# 00A-024_FRDM_Protoboard.net
KiCad netlist of a schematic drawn in EAGLE
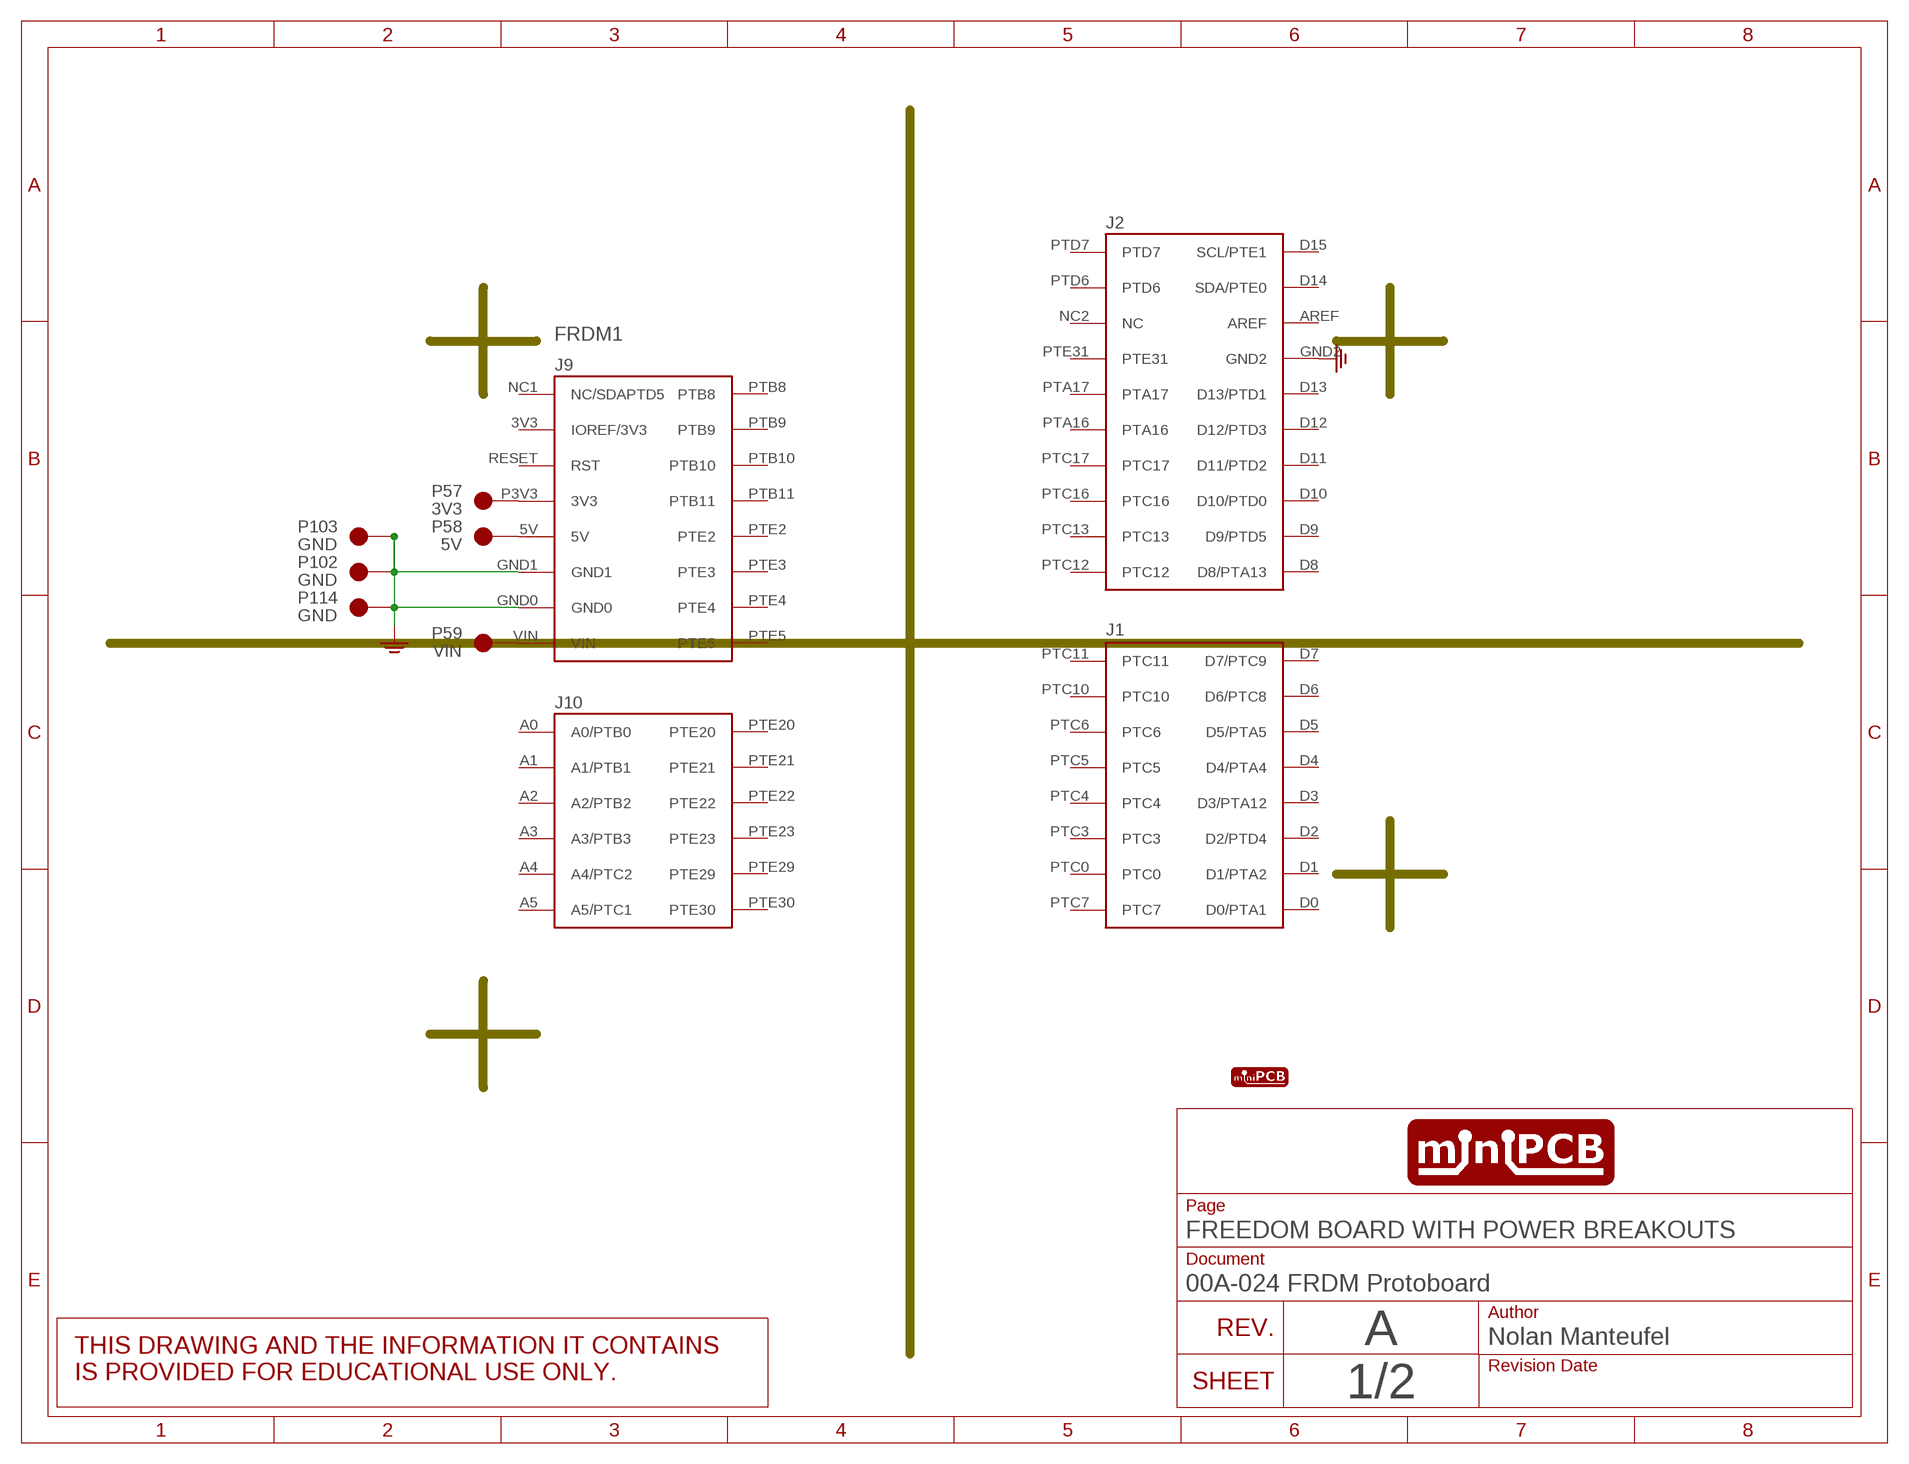
[diagram p0: schematic, sheet 1]
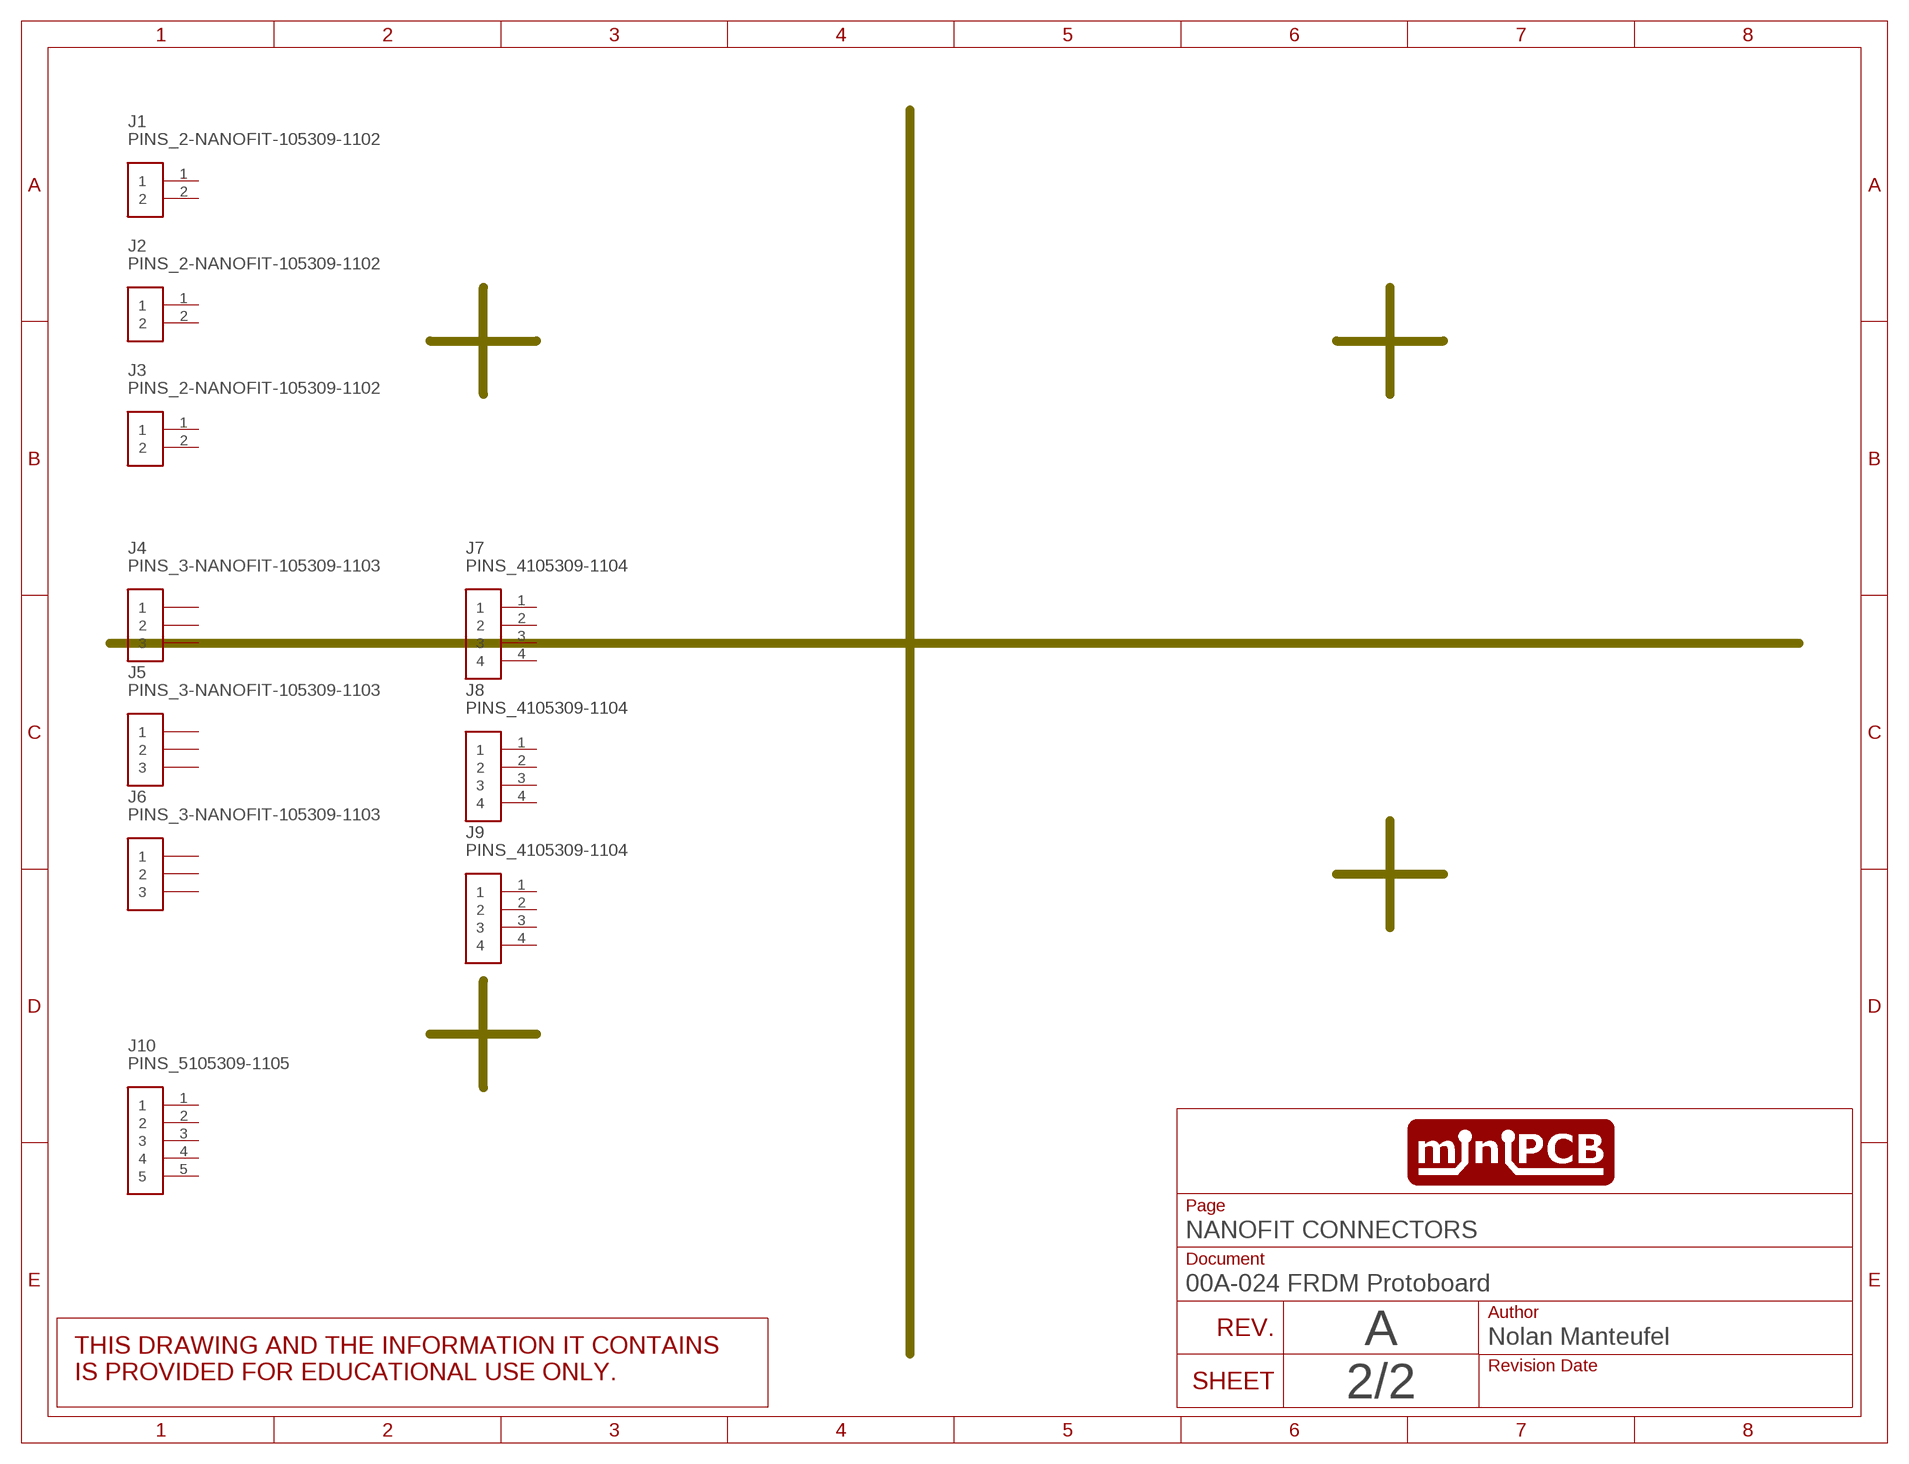
[diagram p1: schematic, sheet 2]

(export (version "E")
  (design (tool "Eeschema 10.0.6"))
  (components
    (comp (ref "FRDM1")
      (value "FRDM-KL25ZNORMAL")
      (footprint "eagle-import:FRDM_KL25Z_NORMAL")
      (fields (field (name "MF") "NXP USA") (field (name "MP") "FRDM-KL25Z"))
      (libsource (lib "eagle-import") (part "FRDM-KL25ZNORMAL"))
    )
    (comp (ref "P57")
      (value "3V3")
      (footprint "eagle-import:PINS_1-3P_VALUE")
      (libsource (lib "eagle-import") (part "PINS_13P_VALUE"))
    )
    (comp (ref "P58")
      (value "5V")
      (footprint "eagle-import:PINS_1-3P_VALUE")
      (libsource (lib "eagle-import") (part "PINS_13P_VALUE"))
    )
    (comp (ref "P59")
      (value "VIN")
      (footprint "eagle-import:PINS_1-3P_VALUE")
      (libsource (lib "eagle-import") (part "PINS_13P_VALUE"))
    )
    (comp (ref "P102")
      (value "GND")
      (footprint "eagle-import:PINS_1-3P_VALUE")
      (libsource (lib "eagle-import") (part "PINS_13P_VALUE"))
    )
    (comp (ref "P103")
      (value "GND")
      (footprint "eagle-import:PINS_1-3P_VALUE")
      (libsource (lib "eagle-import") (part "PINS_13P_VALUE"))
    )
    (comp (ref "P114")
      (value "GND")
      (footprint "eagle-import:PINS_1-3P_VALUE")
      (libsource (lib "eagle-import") (part "PINS_13P_VALUE"))
    )
    (comp (ref "U$1")
      (value "MINIPCB_LOGO")
      (footprint "eagle-import:MINIPCB-LOGO")
      (libsource (lib "eagle-import") (part "MINIPCB_LOGO"))
    )
    (comp (ref "J1")
      (value "PINS_2-NANOFIT-105309-1102")
      (footprint "eagle-import:PINS_2-NANOFIT")
      (libsource (lib "eagle-import") (part "PINS_2-NANOFIT-105309-1102"))
    )
    (comp (ref "J2")
      (value "PINS_2-NANOFIT-105309-1102")
      (footprint "eagle-import:PINS_2-NANOFIT")
      (libsource (lib "eagle-import") (part "PINS_2-NANOFIT-105309-1102"))
    )
    (comp (ref "J3")
      (value "PINS_2-NANOFIT-105309-1102")
      (footprint "eagle-import:PINS_2-NANOFIT")
      (libsource (lib "eagle-import") (part "PINS_2-NANOFIT-105309-1102"))
    )
    (comp (ref "J4")
      (value "PINS_3-NANOFIT-105309-1103")
      (footprint "eagle-import:PINS_3-NANOFIT")
      (libsource (lib "eagle-import") (part "PINS_3-NANOFIT-105309-1103"))
    )
    (comp (ref "J5")
      (value "PINS_3-NANOFIT-105309-1103")
      (footprint "eagle-import:PINS_3-NANOFIT")
      (libsource (lib "eagle-import") (part "PINS_3-NANOFIT-105309-1103"))
    )
    (comp (ref "J6")
      (value "PINS_3-NANOFIT-105309-1103")
      (footprint "eagle-import:PINS_3-NANOFIT")
      (libsource (lib "eagle-import") (part "PINS_3-NANOFIT-105309-1103"))
    )
    (comp (ref "J7")
      (value "PINS_4105309-1104")
      (footprint "eagle-import:PINS_4-NANOFIT")
      (libsource (lib "eagle-import") (part "PINS_4105309-1104"))
    )
    (comp (ref "J8")
      (value "PINS_4105309-1104")
      (footprint "eagle-import:PINS_4-NANOFIT")
      (libsource (lib "eagle-import") (part "PINS_4105309-1104"))
    )
    (comp (ref "J9")
      (value "PINS_4105309-1104")
      (footprint "eagle-import:PINS_4-NANOFIT")
      (libsource (lib "eagle-import") (part "PINS_4105309-1104"))
    )
    (comp (ref "J10")
      (value "PINS_5105309-1105")
      (footprint "eagle-import:PINS_5-NANOFIT")
      (libsource (lib "eagle-import") (part "PINS_5105309-1105"))
    )
  )
  (nets
    (net (code "1") (name "GND") (class "Default")
      (node (ref "FRDM1") (pin "GND0") (pinfunction "GND0_GND0") (pintype "bidirectional"))
      (node (ref "FRDM1") (pin "GND1") (pinfunction "GND1_GND1") (pintype "bidirectional"))
      (node (ref "FRDM1") (pin "GND2") (pinfunction "GND2_GND2") (pintype "bidirectional"))
      (node (ref "P102") (pin "1") (pinfunction "1_1") (pintype "bidirectional"))
      (node (ref "P102") (pin "2") (pinfunction "1_2") (pintype "bidirectional"))
      (node (ref "P102") (pin "3") (pinfunction "1_3") (pintype "bidirectional"))
      (node (ref "P103") (pin "1") (pinfunction "1_1") (pintype "bidirectional"))
      (node (ref "P103") (pin "2") (pinfunction "1_2") (pintype "bidirectional"))
      (node (ref "P103") (pin "3") (pinfunction "1_3") (pintype "bidirectional"))
      (node (ref "P114") (pin "1") (pinfunction "1_1") (pintype "bidirectional"))
      (node (ref "P114") (pin "2") (pinfunction "1_2") (pintype "bidirectional"))
      (node (ref "P114") (pin "3") (pinfunction "1_3") (pintype "bidirectional"))
    )
    (net (code "2") (name "Net-(FRDM1-3V3)") (class "Default")
      (node (ref "FRDM1") (pin "P3V3") (pinfunction "3V3_P3V3") (pintype "bidirectional"))
      (node (ref "P57") (pin "1") (pinfunction "1_1") (pintype "bidirectional"))
      (node (ref "P57") (pin "2") (pinfunction "1_2") (pintype "bidirectional"))
      (node (ref "P57") (pin "3") (pinfunction "1_3") (pintype "bidirectional"))
    )
    (net (code "3") (name "Net-(FRDM1-Pad5V)") (class "Default")
      (node (ref "FRDM1") (pin "5V") (pinfunction "5V_5V") (pintype "bidirectional"))
      (node (ref "P58") (pin "1") (pinfunction "1_1") (pintype "bidirectional"))
      (node (ref "P58") (pin "2") (pinfunction "1_2") (pintype "bidirectional"))
      (node (ref "P58") (pin "3") (pinfunction "1_3") (pintype "bidirectional"))
    )
    (net (code "4") (name "Net-(FRDM1-PadVIN)") (class "Default")
      (node (ref "FRDM1") (pin "VIN") (pinfunction "VIN_VIN") (pintype "bidirectional"))
      (node (ref "P59") (pin "1") (pinfunction "1_1") (pintype "bidirectional"))
      (node (ref "P59") (pin "2") (pinfunction "1_2") (pintype "bidirectional"))
      (node (ref "P59") (pin "3") (pinfunction "1_3") (pintype "bidirectional"))
    )
    (net (code "5") (name "unconnected-(FRDM1-A0{slash}PTB0-PadA0)") (class "Default")
      (node (ref "FRDM1") (pin "A0") (pinfunction "A0/PTB0_A0") (pintype "bidirectional"))
    )
    (net (code "6") (name "unconnected-(FRDM1-A1{slash}PTB1-PadA1)") (class "Default")
      (node (ref "FRDM1") (pin "A1") (pinfunction "A1/PTB1_A1") (pintype "bidirectional"))
    )
    (net (code "7") (name "unconnected-(FRDM1-A2{slash}PTB2-PadA2)") (class "Default")
      (node (ref "FRDM1") (pin "A2") (pinfunction "A2/PTB2_A2") (pintype "bidirectional"))
    )
    (net (code "8") (name "unconnected-(FRDM1-A3{slash}PTB3-PadA3)") (class "Default")
      (node (ref "FRDM1") (pin "A3") (pinfunction "A3/PTB3_A3") (pintype "bidirectional"))
    )
    (net (code "9") (name "unconnected-(FRDM1-A4{slash}PTC2-PadA4)") (class "Default")
      (node (ref "FRDM1") (pin "A4") (pinfunction "A4/PTC2_A4") (pintype "bidirectional"))
    )
    (net (code "10") (name "unconnected-(FRDM1-A5{slash}PTC1-PadA5)") (class "Default")
      (node (ref "FRDM1") (pin "A5") (pinfunction "A5/PTC1_A5") (pintype "bidirectional"))
    )
    (net (code "11") (name "unconnected-(FRDM1-D0{slash}PTA1-PadD0)") (class "Default")
      (node (ref "FRDM1") (pin "D0") (pinfunction "D0/PTA1_D0") (pintype "bidirectional"))
    )
    (net (code "12") (name "unconnected-(FRDM1-D1{slash}PTA2-PadD1)") (class "Default")
      (node (ref "FRDM1") (pin "D1") (pinfunction "D1/PTA2_D1") (pintype "bidirectional"))
    )
    (net (code "13") (name "unconnected-(FRDM1-D2{slash}PTD4-PadD2)") (class "Default")
      (node (ref "FRDM1") (pin "D2") (pinfunction "D2/PTD4_D2") (pintype "bidirectional"))
    )
    (net (code "14") (name "unconnected-(FRDM1-D3{slash}PTA12-PadD3)") (class "Default")
      (node (ref "FRDM1") (pin "D3") (pinfunction "D3/PTA12_D3") (pintype "bidirectional"))
    )
    (net (code "15") (name "unconnected-(FRDM1-D4{slash}PTA4-PadD4)") (class "Default")
      (node (ref "FRDM1") (pin "D4") (pinfunction "D4/PTA4_D4") (pintype "bidirectional"))
    )
    (net (code "16") (name "unconnected-(FRDM1-D5{slash}PTA5-PadD5)") (class "Default")
      (node (ref "FRDM1") (pin "D5") (pinfunction "D5/PTA5_D5") (pintype "bidirectional"))
    )
    (net (code "17") (name "unconnected-(FRDM1-D6{slash}PTC8-PadD6)") (class "Default")
      (node (ref "FRDM1") (pin "D6") (pinfunction "D6/PTC8_D6") (pintype "bidirectional"))
    )
    (net (code "18") (name "unconnected-(FRDM1-D7{slash}PTC9-PadD7)") (class "Default")
      (node (ref "FRDM1") (pin "D7") (pinfunction "D7/PTC9_D7") (pintype "bidirectional"))
    )
    (net (code "19") (name "unconnected-(FRDM1-D8{slash}PTA13-PadD8)") (class "Default")
      (node (ref "FRDM1") (pin "D8") (pinfunction "D8/PTA13_D8") (pintype "bidirectional"))
    )
    (net (code "20") (name "unconnected-(FRDM1-D9{slash}PTD5-PadD9)") (class "Default")
      (node (ref "FRDM1") (pin "D9") (pinfunction "D9/PTD5_D9") (pintype "bidirectional"))
    )
    (net (code "21") (name "unconnected-(FRDM1-D10{slash}PTD0-PadD10)") (class "Default")
      (node (ref "FRDM1") (pin "D10") (pinfunction "D10/PTD0_D10") (pintype "bidirectional"))
    )
    (net (code "22") (name "unconnected-(FRDM1-D11{slash}PTD2-PadD11)") (class "Default")
      (node (ref "FRDM1") (pin "D11") (pinfunction "D11/PTD2_D11") (pintype "bidirectional"))
    )
    (net (code "23") (name "unconnected-(FRDM1-D12{slash}PTD3-PadD12)") (class "Default")
      (node (ref "FRDM1") (pin "D12") (pinfunction "D12/PTD3_D12") (pintype "bidirectional"))
    )
    (net (code "24") (name "unconnected-(FRDM1-D13{slash}PTD1-PadD13)") (class "Default")
      (node (ref "FRDM1") (pin "D13") (pinfunction "D13/PTD1_D13") (pintype "bidirectional"))
    )
    (net (code "25") (name "unconnected-(FRDM1-IOREF{slash}3V3-Pad3V3)") (class "Default")
      (node (ref "FRDM1") (pin "3V3") (pinfunction "IOREF/3V3_3V3") (pintype "bidirectional"))
    )
    (net (code "26") (name "unconnected-(FRDM1-NC-PadNC2)") (class "Default")
      (node (ref "FRDM1") (pin "NC2") (pinfunction "NC_NC2") (pintype "bidirectional"))
    )
    (net (code "27") (name "unconnected-(FRDM1-NC{slash}SDAPTD5-PadNC1)") (class "Default")
      (node (ref "FRDM1") (pin "NC1") (pinfunction "NC/SDAPTD5_NC1") (pintype "bidirectional"))
    )
    (net (code "28") (name "unconnected-(FRDM1-PadAREF)") (class "Default")
      (node (ref "FRDM1") (pin "AREF") (pinfunction "AREF_AREF") (pintype "bidirectional"))
    )
    (net (code "29") (name "unconnected-(FRDM1-PadPTA16)") (class "Default")
      (node (ref "FRDM1") (pin "PTA16") (pinfunction "PTA16_PTA16") (pintype "bidirectional"))
    )
    (net (code "30") (name "unconnected-(FRDM1-PadPTA17)") (class "Default")
      (node (ref "FRDM1") (pin "PTA17") (pinfunction "PTA17_PTA17") (pintype "bidirectional"))
    )
    (net (code "31") (name "unconnected-(FRDM1-PadPTB8)") (class "Default")
      (node (ref "FRDM1") (pin "PTB8") (pinfunction "PTB8_PTB8") (pintype "bidirectional"))
    )
    (net (code "32") (name "unconnected-(FRDM1-PadPTB9)") (class "Default")
      (node (ref "FRDM1") (pin "PTB9") (pinfunction "PTB9_PTB9") (pintype "bidirectional"))
    )
    (net (code "33") (name "unconnected-(FRDM1-PadPTB10)") (class "Default")
      (node (ref "FRDM1") (pin "PTB10") (pinfunction "PTB10_PTB10") (pintype "bidirectional"))
    )
    (net (code "34") (name "unconnected-(FRDM1-PadPTB11)") (class "Default")
      (node (ref "FRDM1") (pin "PTB11") (pinfunction "PTB11_PTB11") (pintype "bidirectional"))
    )
    (net (code "35") (name "unconnected-(FRDM1-PadPTC0)") (class "Default")
      (node (ref "FRDM1") (pin "PTC0") (pinfunction "PTC0_PTC0") (pintype "bidirectional"))
    )
    (net (code "36") (name "unconnected-(FRDM1-PadPTC3)") (class "Default")
      (node (ref "FRDM1") (pin "PTC3") (pinfunction "PTC3_PTC3") (pintype "bidirectional"))
    )
    (net (code "37") (name "unconnected-(FRDM1-PadPTC4)") (class "Default")
      (node (ref "FRDM1") (pin "PTC4") (pinfunction "PTC4_PTC4") (pintype "bidirectional"))
    )
    (net (code "38") (name "unconnected-(FRDM1-PadPTC5)") (class "Default")
      (node (ref "FRDM1") (pin "PTC5") (pinfunction "PTC5_PTC5") (pintype "bidirectional"))
    )
    (net (code "39") (name "unconnected-(FRDM1-PadPTC6)") (class "Default")
      (node (ref "FRDM1") (pin "PTC6") (pinfunction "PTC6_PTC6") (pintype "bidirectional"))
    )
    (net (code "40") (name "unconnected-(FRDM1-PadPTC7)") (class "Default")
      (node (ref "FRDM1") (pin "PTC7") (pinfunction "PTC7_PTC7") (pintype "bidirectional"))
    )
    (net (code "41") (name "unconnected-(FRDM1-PadPTC10)") (class "Default")
      (node (ref "FRDM1") (pin "PTC10") (pinfunction "PTC10_PTC10") (pintype "bidirectional"))
    )
    (net (code "42") (name "unconnected-(FRDM1-PadPTC11)") (class "Default")
      (node (ref "FRDM1") (pin "PTC11") (pinfunction "PTC11_PTC11") (pintype "bidirectional"))
    )
    (net (code "43") (name "unconnected-(FRDM1-PadPTC12)") (class "Default")
      (node (ref "FRDM1") (pin "PTC12") (pinfunction "PTC12_PTC12") (pintype "bidirectional"))
    )
    (net (code "44") (name "unconnected-(FRDM1-PadPTC13)") (class "Default")
      (node (ref "FRDM1") (pin "PTC13") (pinfunction "PTC13_PTC13") (pintype "bidirectional"))
    )
    (net (code "45") (name "unconnected-(FRDM1-PadPTC16)") (class "Default")
      (node (ref "FRDM1") (pin "PTC16") (pinfunction "PTC16_PTC16") (pintype "bidirectional"))
    )
    (net (code "46") (name "unconnected-(FRDM1-PadPTC17)") (class "Default")
      (node (ref "FRDM1") (pin "PTC17") (pinfunction "PTC17_PTC17") (pintype "bidirectional"))
    )
    (net (code "47") (name "unconnected-(FRDM1-PadPTD6)") (class "Default")
      (node (ref "FRDM1") (pin "PTD6") (pinfunction "PTD6_PTD6") (pintype "bidirectional"))
    )
    (net (code "48") (name "unconnected-(FRDM1-PadPTD7)") (class "Default")
      (node (ref "FRDM1") (pin "PTD7") (pinfunction "PTD7_PTD7") (pintype "bidirectional"))
    )
    (net (code "49") (name "unconnected-(FRDM1-PadPTE2)") (class "Default")
      (node (ref "FRDM1") (pin "PTE2") (pinfunction "PTE2_PTE2") (pintype "bidirectional"))
    )
    (net (code "50") (name "unconnected-(FRDM1-PadPTE3)") (class "Default")
      (node (ref "FRDM1") (pin "PTE3") (pinfunction "PTE3_PTE3") (pintype "bidirectional"))
    )
    (net (code "51") (name "unconnected-(FRDM1-PadPTE4)") (class "Default")
      (node (ref "FRDM1") (pin "PTE4") (pinfunction "PTE4_PTE4") (pintype "bidirectional"))
    )
    (net (code "52") (name "unconnected-(FRDM1-PadPTE5)") (class "Default")
      (node (ref "FRDM1") (pin "PTE5") (pinfunction "PTE5_PTE5") (pintype "bidirectional"))
    )
    (net (code "53") (name "unconnected-(FRDM1-PadPTE20)") (class "Default")
      (node (ref "FRDM1") (pin "PTE20") (pinfunction "PTE20_PTE20") (pintype "bidirectional"))
    )
    (net (code "54") (name "unconnected-(FRDM1-PadPTE21)") (class "Default")
      (node (ref "FRDM1") (pin "PTE21") (pinfunction "PTE21_PTE21") (pintype "bidirectional"))
    )
    (net (code "55") (name "unconnected-(FRDM1-PadPTE22)") (class "Default")
      (node (ref "FRDM1") (pin "PTE22") (pinfunction "PTE22_PTE22") (pintype "bidirectional"))
    )
    (net (code "56") (name "unconnected-(FRDM1-PadPTE23)") (class "Default")
      (node (ref "FRDM1") (pin "PTE23") (pinfunction "PTE23_PTE23") (pintype "bidirectional"))
    )
    (net (code "57") (name "unconnected-(FRDM1-PadPTE29)") (class "Default")
      (node (ref "FRDM1") (pin "PTE29") (pinfunction "PTE29_PTE29") (pintype "bidirectional"))
    )
    (net (code "58") (name "unconnected-(FRDM1-PadPTE30)") (class "Default")
      (node (ref "FRDM1") (pin "PTE30") (pinfunction "PTE30_PTE30") (pintype "bidirectional"))
    )
    (net (code "59") (name "unconnected-(FRDM1-PadPTE31)") (class "Default")
      (node (ref "FRDM1") (pin "PTE31") (pinfunction "PTE31_PTE31") (pintype "bidirectional"))
    )
    (net (code "60") (name "unconnected-(FRDM1-RST-PadRESET)") (class "Default")
      (node (ref "FRDM1") (pin "RESET") (pinfunction "RST_RESET") (pintype "bidirectional"))
    )
    (net (code "61") (name "unconnected-(FRDM1-SCL{slash}PTE1-PadD15)") (class "Default")
      (node (ref "FRDM1") (pin "D15") (pinfunction "SCL/PTE1_D15") (pintype "bidirectional"))
    )
    (net (code "62") (name "unconnected-(FRDM1-SDA{slash}PTE0-PadD14)") (class "Default")
      (node (ref "FRDM1") (pin "D14") (pinfunction "SDA/PTE0_D14") (pintype "bidirectional"))
    )
    (net (code "63") (name "unconnected-(J1-Pad1)") (class "Default")
      (node (ref "J1") (pin "1") (pinfunction "1_1") (pintype "bidirectional"))
    )
    (net (code "64") (name "unconnected-(J1-Pad2)") (class "Default")
      (node (ref "J1") (pin "2") (pinfunction "2_2") (pintype "bidirectional"))
    )
    (net (code "65") (name "unconnected-(J2-Pad1)") (class "Default")
      (node (ref "J2") (pin "1") (pinfunction "1_1") (pintype "bidirectional"))
    )
    (net (code "66") (name "unconnected-(J2-Pad2)") (class "Default")
      (node (ref "J2") (pin "2") (pinfunction "2_2") (pintype "bidirectional"))
    )
    (net (code "67") (name "unconnected-(J3-Pad1)") (class "Default")
      (node (ref "J3") (pin "1") (pinfunction "1_1") (pintype "bidirectional"))
    )
    (net (code "68") (name "unconnected-(J3-Pad2)") (class "Default")
      (node (ref "J3") (pin "2") (pinfunction "2_2") (pintype "bidirectional"))
    )
    (net (code "69") (name "unconnected-(J4-Pad1)") (class "Default")
      (node (ref "J4") (pin "1") (pinfunction "1_1") (pintype "bidirectional"))
    )
    (net (code "70") (name "unconnected-(J4-Pad2)") (class "Default")
      (node (ref "J4") (pin "2") (pinfunction "2_2") (pintype "bidirectional"))
    )
    (net (code "71") (name "unconnected-(J4-Pad3)") (class "Default")
      (node (ref "J4") (pin "3") (pinfunction "3_3") (pintype "bidirectional"))
    )
    (net (code "72") (name "unconnected-(J5-Pad1)") (class "Default")
      (node (ref "J5") (pin "1") (pinfunction "1_1") (pintype "bidirectional"))
    )
    (net (code "73") (name "unconnected-(J5-Pad2)") (class "Default")
      (node (ref "J5") (pin "2") (pinfunction "2_2") (pintype "bidirectional"))
    )
    (net (code "74") (name "unconnected-(J5-Pad3)") (class "Default")
      (node (ref "J5") (pin "3") (pinfunction "3_3") (pintype "bidirectional"))
    )
    (net (code "75") (name "unconnected-(J6-Pad1)") (class "Default")
      (node (ref "J6") (pin "1") (pinfunction "1_1") (pintype "bidirectional"))
    )
    (net (code "76") (name "unconnected-(J6-Pad2)") (class "Default")
      (node (ref "J6") (pin "2") (pinfunction "2_2") (pintype "bidirectional"))
    )
    (net (code "77") (name "unconnected-(J6-Pad3)") (class "Default")
      (node (ref "J6") (pin "3") (pinfunction "3_3") (pintype "bidirectional"))
    )
    (net (code "78") (name "unconnected-(J7-Pad1)") (class "Default")
      (node (ref "J7") (pin "1") (pinfunction "1_1") (pintype "bidirectional"))
    )
    (net (code "79") (name "unconnected-(J7-Pad2)") (class "Default")
      (node (ref "J7") (pin "2") (pinfunction "2_2") (pintype "bidirectional"))
    )
    (net (code "80") (name "unconnected-(J7-Pad3)") (class "Default")
      (node (ref "J7") (pin "3") (pinfunction "3_3") (pintype "bidirectional"))
    )
    (net (code "81") (name "unconnected-(J7-Pad4)") (class "Default")
      (node (ref "J7") (pin "4") (pinfunction "4_4") (pintype "bidirectional"))
    )
    (net (code "82") (name "unconnected-(J8-Pad1)") (class "Default")
      (node (ref "J8") (pin "1") (pinfunction "1_1") (pintype "bidirectional"))
    )
    (net (code "83") (name "unconnected-(J8-Pad2)") (class "Default")
      (node (ref "J8") (pin "2") (pinfunction "2_2") (pintype "bidirectional"))
    )
    (net (code "84") (name "unconnected-(J8-Pad3)") (class "Default")
      (node (ref "J8") (pin "3") (pinfunction "3_3") (pintype "bidirectional"))
    )
    (net (code "85") (name "unconnected-(J8-Pad4)") (class "Default")
      (node (ref "J8") (pin "4") (pinfunction "4_4") (pintype "bidirectional"))
    )
    (net (code "86") (name "unconnected-(J9-Pad1)") (class "Default")
      (node (ref "J9") (pin "1") (pinfunction "1_1") (pintype "bidirectional"))
    )
    (net (code "87") (name "unconnected-(J9-Pad2)") (class "Default")
      (node (ref "J9") (pin "2") (pinfunction "2_2") (pintype "bidirectional"))
    )
    (net (code "88") (name "unconnected-(J9-Pad3)") (class "Default")
      (node (ref "J9") (pin "3") (pinfunction "3_3") (pintype "bidirectional"))
    )
    (net (code "89") (name "unconnected-(J9-Pad4)") (class "Default")
      (node (ref "J9") (pin "4") (pinfunction "4_4") (pintype "bidirectional"))
    )
    (net (code "90") (name "unconnected-(J10-Pad1)") (class "Default")
      (node (ref "J10") (pin "1") (pinfunction "1_1") (pintype "bidirectional"))
    )
    (net (code "91") (name "unconnected-(J10-Pad2)") (class "Default")
      (node (ref "J10") (pin "2") (pinfunction "2_2") (pintype "bidirectional"))
    )
    (net (code "92") (name "unconnected-(J10-Pad3)") (class "Default")
      (node (ref "J10") (pin "3") (pinfunction "3_3") (pintype "bidirectional"))
    )
    (net (code "93") (name "unconnected-(J10-Pad4)") (class "Default")
      (node (ref "J10") (pin "4") (pinfunction "4_4") (pintype "bidirectional"))
    )
    (net (code "94") (name "unconnected-(J10-Pad5)") (class "Default")
      (node (ref "J10") (pin "5") (pinfunction "5_5") (pintype "bidirectional"))
    )
  )
)
